# BLUENRG-MS.net
KiCad netlist of a schematic drawn in EAGLE
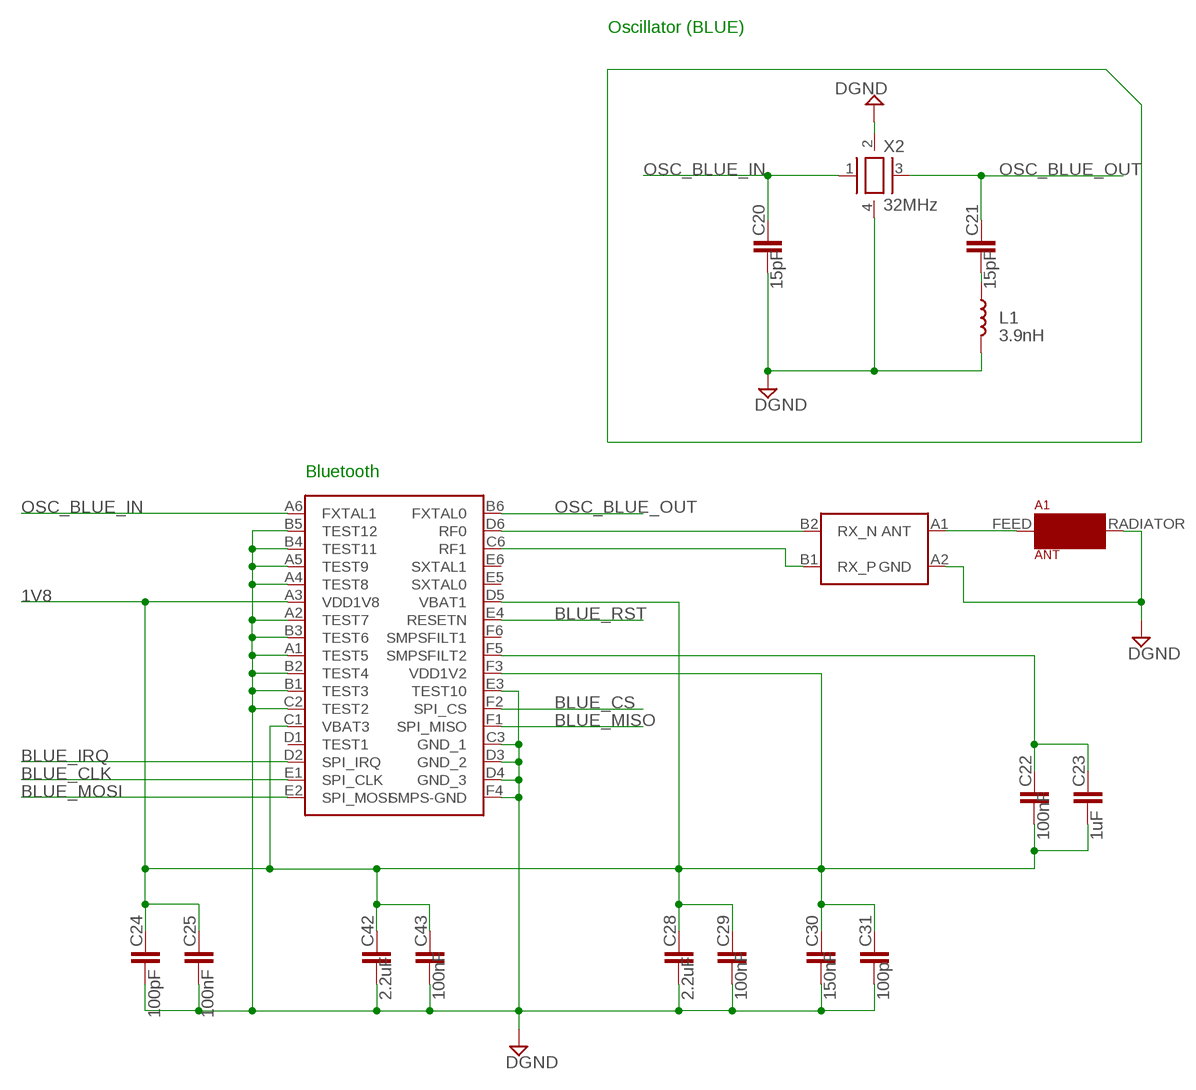
[diagram p0: schematic, sheet 1]

(export (version "E")
  (design (tool "Eeschema 10.0.6"))
  (components
    (comp (ref "A1")
      (value "ANT")
      (footprint "eagle-import:ANTPACK")
      (libsource (lib "eagle-import") (part "ANT"))
    )
    (comp (ref "C20")
      (value "15pF")
      (footprint "eagle-import:0201_X30")
      (libsource (lib "eagle-import") (part "C_NP0603"))
    )
    (comp (ref "C21")
      (value "15pF")
      (footprint "eagle-import:0201_X30")
      (libsource (lib "eagle-import") (part "C_NP0603"))
    )
    (comp (ref "C22")
      (value "100nF")
      (footprint "eagle-import:0201_X30")
      (libsource (lib "eagle-import") (part "C_NP0603"))
    )
    (comp (ref "C23")
      (value "1uF")
      (footprint "eagle-import:0201_X30")
      (libsource (lib "eagle-import") (part "C_NP0603"))
    )
    (comp (ref "C24")
      (value "100pF")
      (footprint "eagle-import:0201_X30")
      (libsource (lib "eagle-import") (part "C_NP0603"))
    )
    (comp (ref "C25")
      (value "100nF")
      (footprint "eagle-import:0201_X30")
      (libsource (lib "eagle-import") (part "C_NP0603"))
    )
    (comp (ref "C28")
      (value "2.2uF")
      (footprint "eagle-import:0201_X30")
      (libsource (lib "eagle-import") (part "C_NP0603"))
    )
    (comp (ref "C29")
      (value "100nF")
      (footprint "eagle-import:0201_X30")
      (libsource (lib "eagle-import") (part "C_NP0603"))
    )
    (comp (ref "C30")
      (value "150nF")
      (footprint "eagle-import:0201_X30")
      (libsource (lib "eagle-import") (part "C_NP0603"))
    )
    (comp (ref "C31")
      (value "100p")
      (footprint "eagle-import:0201_X30")
      (libsource (lib "eagle-import") (part "C_NP0603"))
    )
    (comp (ref "C42")
      (value "2.2uF")
      (footprint "eagle-import:0201_X30")
      (libsource (lib "eagle-import") (part "C_NP0603"))
    )
    (comp (ref "C43")
      (value "100nF")
      (footprint "eagle-import:0201_X30")
      (libsource (lib "eagle-import") (part "C_NP0603"))
    )
    (comp (ref "L1")
      (value "3.9nH")
      (footprint "eagle-import:0201_X30")
      (libsource (lib "eagle-import") (part "L"))
    )
    (comp (ref "L2")
      (value "BALF-NRG-01D3")
      (footprint "eagle-import:FLIPCHIP")
      (libsource (lib "eagle-import") (part "BALF-NRG-01D3"))
    )
    (comp (ref "U3")
      (value "BLUENRG-MS")
      (footprint "eagle-import:WLCSP34")
      (libsource (lib "eagle-import") (part "BLUENRG-MS"))
    )
    (comp (ref "X2")
      (value "32MHz")
      (footprint "eagle-import:ABM11W-101")
      (libsource (lib "eagle-import") (part "ABM11W-101"))
    )
  )
  (nets
    (net (code "1") (name "/1V8") (class "Default")
      (node (ref "C22") (pin "2") (pinfunction "2_2") (pintype "passive"))
      (node (ref "C23") (pin "2") (pinfunction "2_2") (pintype "passive"))
      (node (ref "C24") (pin "1") (pinfunction "1_1") (pintype "passive"))
      (node (ref "C25") (pin "1") (pinfunction "1_1") (pintype "passive"))
      (node (ref "C28") (pin "1") (pinfunction "1_1") (pintype "passive"))
      (node (ref "C29") (pin "1") (pinfunction "1_1") (pintype "passive"))
      (node (ref "C30") (pin "1") (pinfunction "1_1") (pintype "passive"))
      (node (ref "C31") (pin "1") (pinfunction "1_1") (pintype "passive"))
      (node (ref "C42") (pin "1") (pinfunction "1_1") (pintype "passive"))
      (node (ref "C43") (pin "1") (pinfunction "1_1") (pintype "passive"))
      (node (ref "U3") (pin "A3") (pinfunction "VDD1V8_A3") (pintype "power_in"))
      (node (ref "U3") (pin "C1") (pinfunction "VBAT3_C1") (pintype "power_in"))
      (node (ref "U3") (pin "D5") (pinfunction "VBAT1_D5") (pintype "power_in"))
      (node (ref "U3") (pin "F3") (pinfunction "VDD1V2_F3") (pintype "power_in"))
    )
    (net (code "2") (name "/BLUE_CLK") (class "Default")
      (node (ref "U3") (pin "E1") (pinfunction "SPI_CLK_E1") (pintype "power_in"))
    )
    (net (code "3") (name "/BLUE_CS") (class "Default")
      (node (ref "U3") (pin "F2") (pinfunction "SPI_CS_F2") (pintype "power_in"))
    )
    (net (code "4") (name "/BLUE_IRQ") (class "Default")
      (node (ref "U3") (pin "D2") (pinfunction "SPI_IRQ_D2") (pintype "power_in"))
    )
    (net (code "5") (name "/BLUE_MISO") (class "Default")
      (node (ref "U3") (pin "F1") (pinfunction "SPI_MISO_F1") (pintype "power_in"))
    )
    (net (code "6") (name "/BLUE_MOSI") (class "Default")
      (node (ref "U3") (pin "E2") (pinfunction "SPI_MOSI_E2") (pintype "power_in"))
    )
    (net (code "7") (name "/BLUE_RST") (class "Default")
      (node (ref "U3") (pin "E4") (pinfunction "RESETN_E4") (pintype "power_in"))
    )
    (net (code "8") (name "/OSC_BLUE_IN") (class "Default")
      (node (ref "C20") (pin "1") (pinfunction "1_1") (pintype "passive"))
      (node (ref "U3") (pin "A6") (pinfunction "FXTAL1_A6") (pintype "power_in"))
      (node (ref "X2") (pin "1") (pinfunction "P$1_1") (pintype "bidirectional"))
    )
    (net (code "9") (name "/OSC_BLUE_OUT") (class "Default")
      (node (ref "C21") (pin "1") (pinfunction "1_1") (pintype "passive"))
      (node (ref "U3") (pin "B6") (pinfunction "FXTAL0_B6") (pintype "power_in"))
      (node (ref "X2") (pin "3") (pinfunction "P$3_3") (pintype "bidirectional"))
    )
    (net (code "10") (name "/SMPSFILT1") (class "Default")
      (node (ref "U3") (pin "F6") (pinfunction "SMPSFILT1_F6") (pintype "power_in"))
    )
    (net (code "11") (name "/SXTAL0") (class "Default")
      (node (ref "U3") (pin "E5") (pinfunction "SXTAL0_E5") (pintype "power_in"))
    )
    (net (code "12") (name "/SXTAL1") (class "Default")
      (node (ref "U3") (pin "E6") (pinfunction "SXTAL1_E6") (pintype "power_in"))
    )
    (net (code "13") (name "/TEST1") (class "Default")
      (node (ref "U3") (pin "D1") (pinfunction "TEST1_D1") (pintype "power_in"))
    )
    (net (code "14") (name "DGND") (class "Default")
      (node (ref "A1") (pin "RADIATOR") (pinfunction "P$2_RADIATOR") (pintype "bidirectional"))
      (node (ref "C20") (pin "2") (pinfunction "2_2") (pintype "passive"))
      (node (ref "C24") (pin "2") (pinfunction "2_2") (pintype "passive"))
      (node (ref "C25") (pin "2") (pinfunction "2_2") (pintype "passive"))
      (node (ref "C28") (pin "2") (pinfunction "2_2") (pintype "passive"))
      (node (ref "C29") (pin "2") (pinfunction "2_2") (pintype "passive"))
      (node (ref "C30") (pin "2") (pinfunction "2_2") (pintype "passive"))
      (node (ref "C31") (pin "2") (pinfunction "2_2") (pintype "passive"))
      (node (ref "C42") (pin "2") (pinfunction "2_2") (pintype "passive"))
      (node (ref "C43") (pin "2") (pinfunction "2_2") (pintype "passive"))
      (node (ref "L1") (pin "2") (pinfunction "2_2") (pintype "bidirectional"))
      (node (ref "L2") (pin "A2") (pinfunction "GND_A2") (pintype "power_in"))
      (node (ref "U3") (pin "A1") (pinfunction "TEST5_A1") (pintype "power_in"))
      (node (ref "U3") (pin "A2") (pinfunction "TEST7_A2") (pintype "power_in"))
      (node (ref "U3") (pin "A4") (pinfunction "TEST8_A4") (pintype "power_in"))
      (node (ref "U3") (pin "A5") (pinfunction "TEST9_A5") (pintype "power_in"))
      (node (ref "U3") (pin "B1") (pinfunction "TEST3_B1") (pintype "power_in"))
      (node (ref "U3") (pin "B2") (pinfunction "TEST4_B2") (pintype "power_in"))
      (node (ref "U3") (pin "B3") (pinfunction "TEST6_B3") (pintype "power_in"))
      (node (ref "U3") (pin "B4") (pinfunction "TEST11_B4") (pintype "power_in"))
      (node (ref "U3") (pin "B5") (pinfunction "TEST12_B5") (pintype "power_in"))
      (node (ref "U3") (pin "C2") (pinfunction "TEST2_C2") (pintype "power_in"))
      (node (ref "U3") (pin "C3") (pinfunction "GND_1_C3") (pintype "power_in"))
      (node (ref "U3") (pin "D3") (pinfunction "GND_2_D3") (pintype "power_in"))
      (node (ref "U3") (pin "D4") (pinfunction "GND_3_D4") (pintype "power_in"))
      (node (ref "U3") (pin "E3") (pinfunction "TEST10_E3") (pintype "power_in"))
      (node (ref "U3") (pin "F4") (pinfunction "SMPS-GND_F4") (pintype "power_in"))
      (node (ref "X2") (pin "2") (pinfunction "P$2_2") (pintype "bidirectional"))
      (node (ref "X2") (pin "4") (pinfunction "P$4_4") (pintype "bidirectional"))
    )
    (net (code "15") (name "Net-(A1-P$1)") (class "Default")
      (node (ref "A1") (pin "FEED") (pinfunction "P$1_FEED") (pintype "bidirectional"))
      (node (ref "L2") (pin "A1") (pinfunction "ANT_A1") (pintype "power_in"))
    )
    (net (code "16") (name "Net-(C21-Pad2)") (class "Default")
      (node (ref "C21") (pin "2") (pinfunction "2_2") (pintype "passive"))
      (node (ref "L1") (pin "1") (pinfunction "1_1") (pintype "bidirectional"))
    )
    (net (code "17") (name "Net-(L2-RX_N)") (class "Default")
      (node (ref "L2") (pin "B2") (pinfunction "RX_N_B2") (pintype "power_in"))
      (node (ref "U3") (pin "D6") (pinfunction "RF0_D6") (pintype "power_in"))
    )
    (net (code "18") (name "Net-(L2-RX_P)") (class "Default")
      (node (ref "L2") (pin "B1") (pinfunction "RX_P_B1") (pintype "power_in"))
      (node (ref "U3") (pin "C6") (pinfunction "RF1_C6") (pintype "power_in"))
    )
    (net (code "19") (name "Net-(U3-SMPSFILT2)") (class "Default")
      (node (ref "C22") (pin "1") (pinfunction "1_1") (pintype "passive"))
      (node (ref "C23") (pin "1") (pinfunction "1_1") (pintype "passive"))
      (node (ref "U3") (pin "F5") (pinfunction "SMPSFILT2_F5") (pintype "power_in"))
    )
  )
)
